# motor.net
KiCad netlist of a schematic drawn in EAGLE
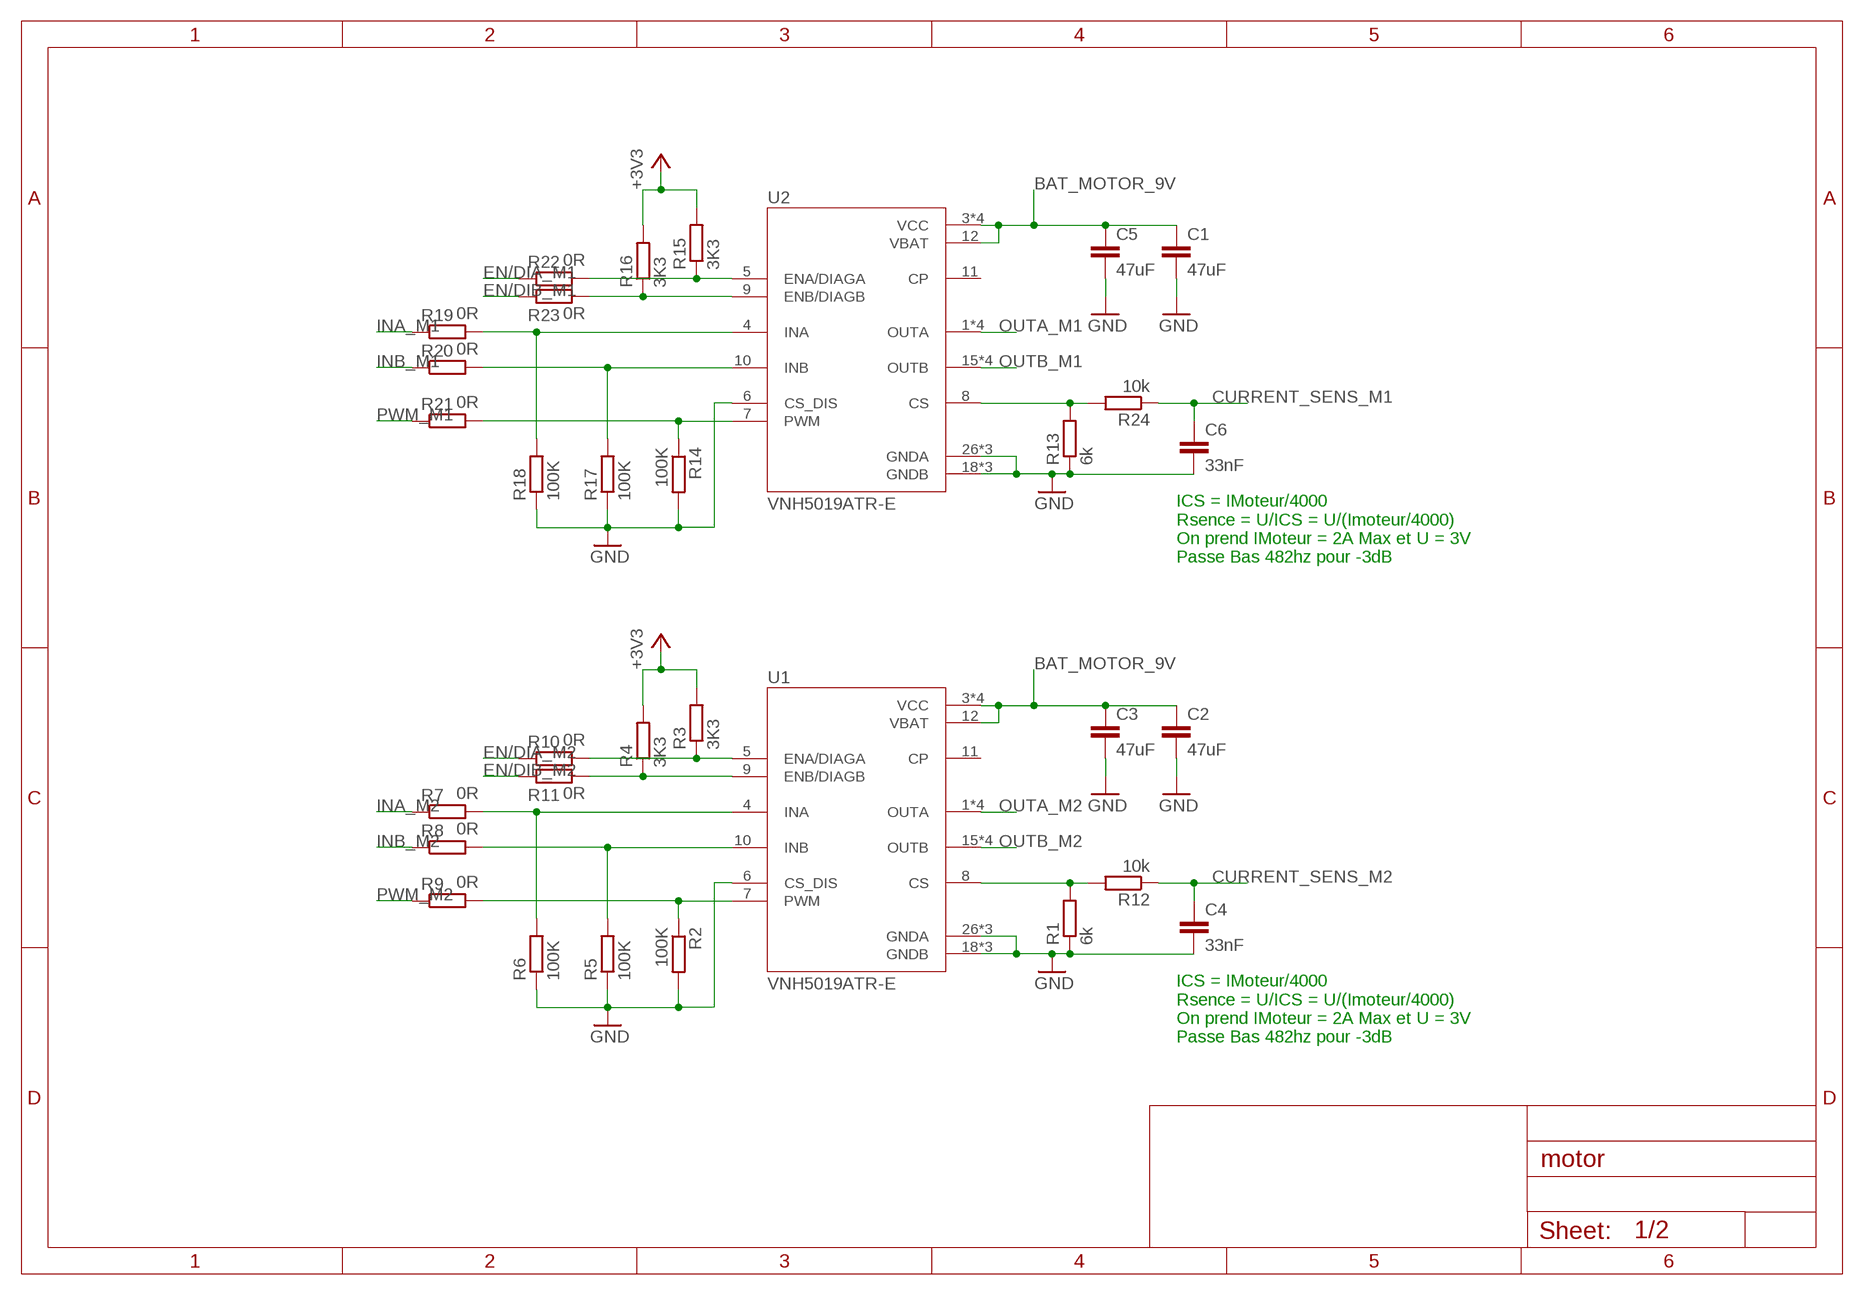
[diagram p0: schematic, sheet 1]
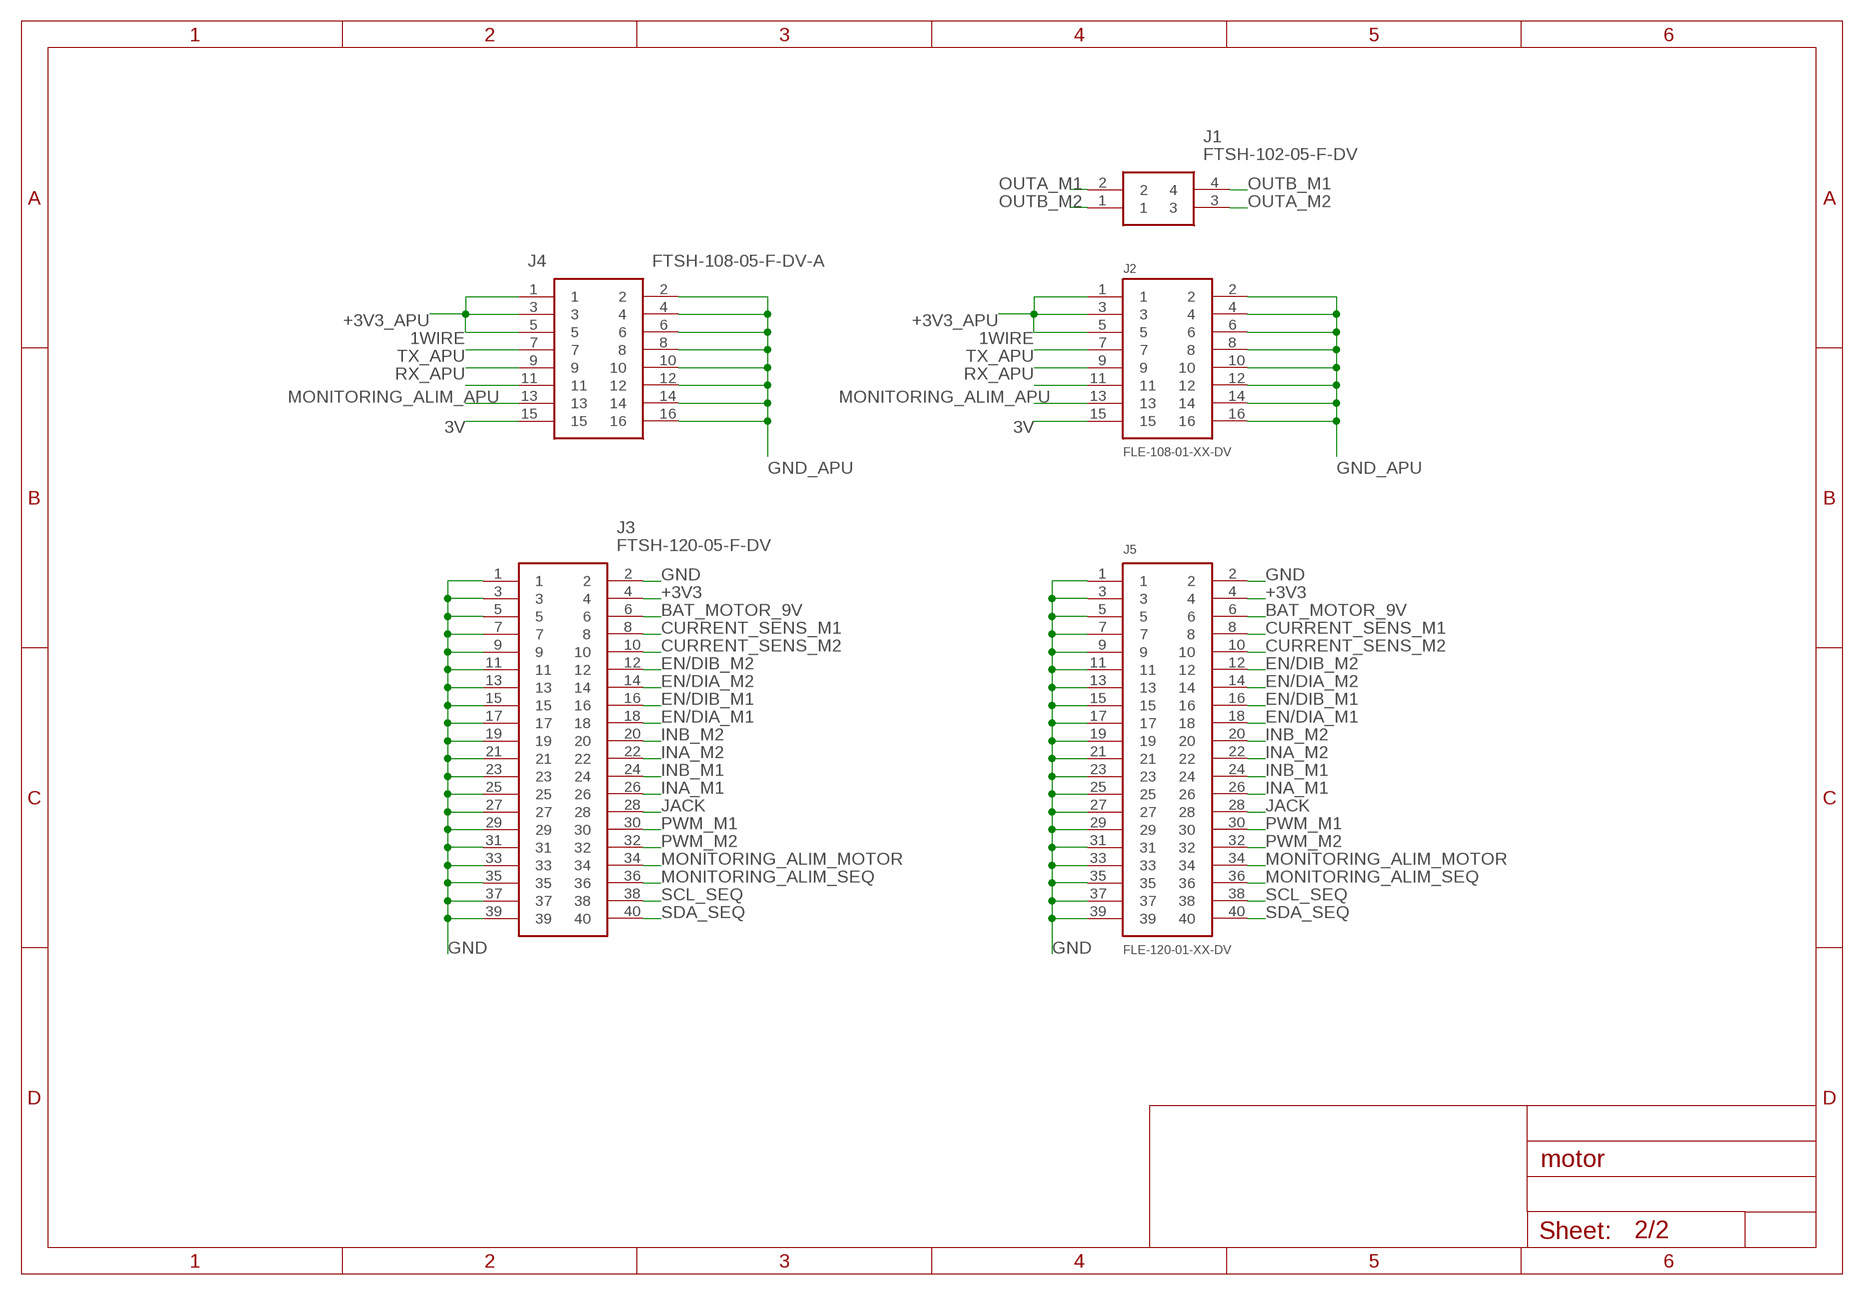
[diagram p1: schematic, sheet 2]

(export (version "E")
  (design (tool "Eeschema 10.0.6"))
  (components
    (comp (ref "J1")
      (value "FTSH-102-05-F-DV")
      (footprint "eagle-import:FTSH-102-XX-YYY-DV")
      (libsource (lib "eagle-import") (part "FTSH-102-05-F-DV"))
    )
    (comp (ref "J2")
      (value "FLE-108-01-XX-DV")
      (footprint "eagle-import:FLE-108-01-XX-DV")
      (fields (field (name "MF") "Samtec") (field (name "MP") "FLE-108-01-G-DV"))
      (libsource (lib "eagle-import") (part "FLE-108-01-XX-DV"))
    )
    (comp (ref "J3")
      (value "FTSH-120-05-F-DV")
      (footprint "eagle-import:FTSH-120-XX-YYY-DV")
      (libsource (lib "eagle-import") (part "FTSH-120-05-F-DV"))
    )
    (comp (ref "J4")
      (value "FTSH-108-05-F-DV-A")
      (footprint "eagle-import:FTSH-108-XX-YYY-DV-A")
      (fields (field (name "MOUSER_PART_NUMBER") "200-FTSH10805FDVA"))
      (libsource (lib "eagle-import") (part "FTSH-108-05-F-DV-A"))
    )
    (comp (ref "J5")
      (value "FLE-120-01-XX-DV")
      (footprint "eagle-import:FLE-120-01-XX-DV")
      (fields (field (name "MF") "Samtec") (field (name "MP") "FLE-120-01-G-DV"))
      (libsource (lib "eagle-import") (part "FLE-120-01-XX-DV"))
    )
    (comp (ref "C1")
      (value "47uF")
      (footprint "eagle-import:C0805")
      (libsource (lib "eagle-import") (part "C-EUC0805"))
    )
    (comp (ref "C2")
      (value "47uF")
      (footprint "eagle-import:C0805")
      (libsource (lib "eagle-import") (part "C-EUC0805"))
    )
    (comp (ref "C3")
      (value "47uF")
      (footprint "eagle-import:C0805")
      (libsource (lib "eagle-import") (part "C-EUC0805"))
    )
    (comp (ref "C4")
      (value "33nF")
      (footprint "eagle-import:C0805")
      (libsource (lib "eagle-import") (part "C-EUC0805"))
    )
    (comp (ref "C5")
      (value "47uF")
      (footprint "eagle-import:C0805")
      (libsource (lib "eagle-import") (part "C-EUC0805"))
    )
    (comp (ref "C6")
      (value "33nF")
      (footprint "eagle-import:C0805")
      (libsource (lib "eagle-import") (part "C-EUC0805"))
    )
    (comp (ref "R1")
      (value "6k")
      (footprint "eagle-import:R0603")
      (libsource (lib "eagle-import") (part "R-EU_R0603"))
    )
    (comp (ref "R2")
      (value "100K")
      (footprint "eagle-import:R0603")
      (libsource (lib "eagle-import") (part "R-EU_R0603"))
    )
    (comp (ref "R3")
      (value "3K3")
      (footprint "eagle-import:R0603")
      (libsource (lib "eagle-import") (part "R-EU_R0603"))
    )
    (comp (ref "R4")
      (value "3K3")
      (footprint "eagle-import:R0603")
      (libsource (lib "eagle-import") (part "R-EU_R0603"))
    )
    (comp (ref "R5")
      (value "100K")
      (footprint "eagle-import:R0603")
      (libsource (lib "eagle-import") (part "R-EU_R0603"))
    )
    (comp (ref "R6")
      (value "100K")
      (footprint "eagle-import:R0603")
      (libsource (lib "eagle-import") (part "R-EU_R0603"))
    )
    (comp (ref "R7")
      (value "0R")
      (footprint "eagle-import:R0603")
      (libsource (lib "eagle-import") (part "R-EU_R0603"))
    )
    (comp (ref "R8")
      (value "0R")
      (footprint "eagle-import:R0603")
      (libsource (lib "eagle-import") (part "R-EU_R0603"))
    )
    (comp (ref "R9")
      (value "0R")
      (footprint "eagle-import:R0603")
      (libsource (lib "eagle-import") (part "R-EU_R0603"))
    )
    (comp (ref "R10")
      (value "0R")
      (footprint "eagle-import:R0603")
      (libsource (lib "eagle-import") (part "R-EU_R0603"))
    )
    (comp (ref "R11")
      (value "0R")
      (footprint "eagle-import:R0603")
      (libsource (lib "eagle-import") (part "R-EU_R0603"))
    )
    (comp (ref "R12")
      (value "10k")
      (footprint "eagle-import:R0603")
      (libsource (lib "eagle-import") (part "R-EU_R0603"))
    )
    (comp (ref "R13")
      (value "6k")
      (footprint "eagle-import:R0603")
      (libsource (lib "eagle-import") (part "R-EU_R0603"))
    )
    (comp (ref "R14")
      (value "100K")
      (footprint "eagle-import:R0603")
      (libsource (lib "eagle-import") (part "R-EU_R0603"))
    )
    (comp (ref "R15")
      (value "3K3")
      (footprint "eagle-import:R0603")
      (libsource (lib "eagle-import") (part "R-EU_R0603"))
    )
    (comp (ref "R16")
      (value "3K3")
      (footprint "eagle-import:R0603")
      (libsource (lib "eagle-import") (part "R-EU_R0603"))
    )
    (comp (ref "R17")
      (value "100K")
      (footprint "eagle-import:R0603")
      (libsource (lib "eagle-import") (part "R-EU_R0603"))
    )
    (comp (ref "R18")
      (value "100K")
      (footprint "eagle-import:R0603")
      (libsource (lib "eagle-import") (part "R-EU_R0603"))
    )
    (comp (ref "R19")
      (value "0R")
      (footprint "eagle-import:R0603")
      (libsource (lib "eagle-import") (part "R-EU_R0603"))
    )
    (comp (ref "R20")
      (value "0R")
      (footprint "eagle-import:R0603")
      (libsource (lib "eagle-import") (part "R-EU_R0603"))
    )
    (comp (ref "R21")
      (value "0R")
      (footprint "eagle-import:R0603")
      (libsource (lib "eagle-import") (part "R-EU_R0603"))
    )
    (comp (ref "R22")
      (value "0R")
      (footprint "eagle-import:R0603")
      (libsource (lib "eagle-import") (part "R-EU_R0603"))
    )
    (comp (ref "R23")
      (value "0R")
      (footprint "eagle-import:R0603")
      (libsource (lib "eagle-import") (part "R-EU_R0603"))
    )
    (comp (ref "R24")
      (value "10k")
      (footprint "eagle-import:R0603")
      (libsource (lib "eagle-import") (part "R-EU_R0603"))
    )
    (comp (ref "U1")
      (value "VNH5019ATR-E")
      (footprint "eagle-import:IC_VNH5019ATR-E")
      (fields (field (name "MF") "STMicroelectronics"))
      (libsource (lib "eagle-import") (part "VNH5019ATR-E"))
    )
    (comp (ref "U2")
      (value "VNH5019ATR-E")
      (footprint "eagle-import:IC_VNH5019ATR-E")
      (fields (field (name "MF") "STMicroelectronics"))
      (libsource (lib "eagle-import") (part "VNH5019ATR-E"))
    )
  )
  (nets
    (net (code "1") (name "+3V3") (class "Default")
      (node (ref "J3") (pin "4") (pinfunction "4_4") (pintype "bidirectional"))
      (node (ref "J5") (pin "4") (pinfunction "4_4") (pintype "bidirectional"))
      (node (ref "R15") (pin "2") (pinfunction "2_2") (pintype "passive"))
      (node (ref "R16") (pin "2") (pinfunction "2_2") (pintype "passive"))
      (node (ref "R3") (pin "2") (pinfunction "2_2") (pintype "passive"))
      (node (ref "R4") (pin "2") (pinfunction "2_2") (pintype "passive"))
    )
    (net (code "2") (name "+3V3_APU") (class "Default")
      (node (ref "J2") (pin "1") (pinfunction "1_1") (pintype "bidirectional"))
      (node (ref "J2") (pin "3") (pinfunction "3_3") (pintype "bidirectional"))
      (node (ref "J2") (pin "5") (pinfunction "5_5") (pintype "bidirectional"))
      (node (ref "J4") (pin "1") (pinfunction "1_1") (pintype "bidirectional"))
      (node (ref "J4") (pin "3") (pinfunction "3_3") (pintype "bidirectional"))
      (node (ref "J4") (pin "5") (pinfunction "5_5") (pintype "bidirectional"))
    )
    (net (code "3") (name "1WIRE") (class "Default")
      (node (ref "J2") (pin "7") (pinfunction "7_7") (pintype "bidirectional"))
      (node (ref "J4") (pin "7") (pinfunction "7_7") (pintype "bidirectional"))
    )
    (net (code "4") (name "3V") (class "Default")
      (node (ref "J2") (pin "15") (pinfunction "15_15") (pintype "bidirectional"))
      (node (ref "J4") (pin "15") (pinfunction "15_15") (pintype "bidirectional"))
    )
    (net (code "5") (name "BAT_MOTOR_9V") (class "Default")
      (node (ref "C1") (pin "1") (pinfunction "1_1") (pintype "passive"))
      (node (ref "C2") (pin "1") (pinfunction "1_1") (pintype "passive"))
      (node (ref "C3") (pin "1") (pinfunction "1_1") (pintype "passive"))
      (node (ref "C5") (pin "1") (pinfunction "1_1") (pintype "passive"))
      (node (ref "J3") (pin "6") (pinfunction "6_6") (pintype "bidirectional"))
      (node (ref "J5") (pin "6") (pinfunction "6_6") (pintype "bidirectional"))
      (node (ref "U1") (pin "12") (pinfunction "VBAT_12") (pintype "power_in"))
      (node (ref "U1") (pin "13") (pinfunction "VCC_13") (pintype "power_in"))
      (node (ref "U1") (pin "23") (pinfunction "VCC_23") (pintype "power_in"))
      (node (ref "U1") (pin "3") (pinfunction "VCC_3") (pintype "power_in"))
      (node (ref "U1") (pin "HS1") (pinfunction "VCC_HS1") (pintype "power_in"))
      (node (ref "U2") (pin "12") (pinfunction "VBAT_12") (pintype "power_in"))
      (node (ref "U2") (pin "13") (pinfunction "VCC_13") (pintype "power_in"))
      (node (ref "U2") (pin "23") (pinfunction "VCC_23") (pintype "power_in"))
      (node (ref "U2") (pin "3") (pinfunction "VCC_3") (pintype "power_in"))
      (node (ref "U2") (pin "HS1") (pinfunction "VCC_HS1") (pintype "power_in"))
    )
    (net (code "6") (name "CURRENT_SENS_M1") (class "Default")
      (node (ref "C6") (pin "1") (pinfunction "1_1") (pintype "passive"))
      (node (ref "J3") (pin "8") (pinfunction "8_8") (pintype "bidirectional"))
      (node (ref "J5") (pin "8") (pinfunction "8_8") (pintype "bidirectional"))
      (node (ref "R24") (pin "1") (pinfunction "1_1") (pintype "passive"))
    )
    (net (code "7") (name "CURRENT_SENS_M2") (class "Default")
      (node (ref "C4") (pin "1") (pinfunction "1_1") (pintype "passive"))
      (node (ref "J3") (pin "10") (pinfunction "10_10") (pintype "bidirectional"))
      (node (ref "J5") (pin "10") (pinfunction "10_10") (pintype "bidirectional"))
      (node (ref "R12") (pin "1") (pinfunction "1_1") (pintype "passive"))
    )
    (net (code "8") (name "EN{slash}DIA_M1") (class "Default")
      (node (ref "J3") (pin "18") (pinfunction "18_18") (pintype "bidirectional"))
      (node (ref "J5") (pin "18") (pinfunction "18_18") (pintype "bidirectional"))
      (node (ref "R22") (pin "1") (pinfunction "1_1") (pintype "passive"))
    )
    (net (code "9") (name "EN{slash}DIA_M2") (class "Default")
      (node (ref "J3") (pin "14") (pinfunction "14_14") (pintype "bidirectional"))
      (node (ref "J5") (pin "14") (pinfunction "14_14") (pintype "bidirectional"))
      (node (ref "R10") (pin "1") (pinfunction "1_1") (pintype "passive"))
    )
    (net (code "10") (name "EN{slash}DIB_M1") (class "Default")
      (node (ref "J3") (pin "16") (pinfunction "16_16") (pintype "bidirectional"))
      (node (ref "J5") (pin "16") (pinfunction "16_16") (pintype "bidirectional"))
      (node (ref "R23") (pin "1") (pinfunction "1_1") (pintype "passive"))
    )
    (net (code "11") (name "EN{slash}DIB_M2") (class "Default")
      (node (ref "J3") (pin "12") (pinfunction "12_12") (pintype "bidirectional"))
      (node (ref "J5") (pin "12") (pinfunction "12_12") (pintype "bidirectional"))
      (node (ref "R11") (pin "1") (pinfunction "1_1") (pintype "passive"))
    )
    (net (code "12") (name "GND") (class "Default")
      (node (ref "C1") (pin "2") (pinfunction "2_2") (pintype "passive"))
      (node (ref "C2") (pin "2") (pinfunction "2_2") (pintype "passive"))
      (node (ref "C3") (pin "2") (pinfunction "2_2") (pintype "passive"))
      (node (ref "C4") (pin "2") (pinfunction "2_2") (pintype "passive"))
      (node (ref "C5") (pin "2") (pinfunction "2_2") (pintype "passive"))
      (node (ref "C6") (pin "2") (pinfunction "2_2") (pintype "passive"))
      (node (ref "J3") (pin "1") (pinfunction "1_1") (pintype "bidirectional"))
      (node (ref "J3") (pin "11") (pinfunction "11_11") (pintype "bidirectional"))
      (node (ref "J3") (pin "13") (pinfunction "13_13") (pintype "bidirectional"))
      (node (ref "J3") (pin "15") (pinfunction "15_15") (pintype "bidirectional"))
      (node (ref "J3") (pin "17") (pinfunction "17_17") (pintype "bidirectional"))
      (node (ref "J3") (pin "19") (pinfunction "19_19") (pintype "bidirectional"))
      (node (ref "J3") (pin "2") (pinfunction "2_2") (pintype "bidirectional"))
      (node (ref "J3") (pin "21") (pinfunction "21_21") (pintype "bidirectional"))
      (node (ref "J3") (pin "23") (pinfunction "23_23") (pintype "bidirectional"))
      (node (ref "J3") (pin "25") (pinfunction "25_25") (pintype "bidirectional"))
      (node (ref "J3") (pin "27") (pinfunction "27_27") (pintype "bidirectional"))
      (node (ref "J3") (pin "29") (pinfunction "29_29") (pintype "bidirectional"))
      (node (ref "J3") (pin "3") (pinfunction "3_3") (pintype "bidirectional"))
      (node (ref "J3") (pin "31") (pinfunction "31_31") (pintype "bidirectional"))
      (node (ref "J3") (pin "33") (pinfunction "33_33") (pintype "bidirectional"))
      (node (ref "J3") (pin "35") (pinfunction "35_35") (pintype "bidirectional"))
      (node (ref "J3") (pin "37") (pinfunction "37_37") (pintype "bidirectional"))
      (node (ref "J3") (pin "39") (pinfunction "39_39") (pintype "bidirectional"))
      (node (ref "J3") (pin "5") (pinfunction "5_5") (pintype "bidirectional"))
      (node (ref "J3") (pin "7") (pinfunction "7_7") (pintype "bidirectional"))
      (node (ref "J3") (pin "9") (pinfunction "9_9") (pintype "bidirectional"))
      (node (ref "J5") (pin "1") (pinfunction "1_1") (pintype "bidirectional"))
      (node (ref "J5") (pin "11") (pinfunction "11_11") (pintype "bidirectional"))
      (node (ref "J5") (pin "13") (pinfunction "13_13") (pintype "bidirectional"))
      (node (ref "J5") (pin "15") (pinfunction "15_15") (pintype "bidirectional"))
      (node (ref "J5") (pin "17") (pinfunction "17_17") (pintype "bidirectional"))
      (node (ref "J5") (pin "19") (pinfunction "19_19") (pintype "bidirectional"))
      (node (ref "J5") (pin "2") (pinfunction "2_2") (pintype "bidirectional"))
      (node (ref "J5") (pin "21") (pinfunction "21_21") (pintype "bidirectional"))
      (node (ref "J5") (pin "23") (pinfunction "23_23") (pintype "bidirectional"))
      (node (ref "J5") (pin "25") (pinfunction "25_25") (pintype "bidirectional"))
      (node (ref "J5") (pin "27") (pinfunction "27_27") (pintype "bidirectional"))
      (node (ref "J5") (pin "29") (pinfunction "29_29") (pintype "bidirectional"))
      (node (ref "J5") (pin "3") (pinfunction "3_3") (pintype "bidirectional"))
      (node (ref "J5") (pin "31") (pinfunction "31_31") (pintype "bidirectional"))
      (node (ref "J5") (pin "33") (pinfunction "33_33") (pintype "bidirectional"))
      (node (ref "J5") (pin "35") (pinfunction "35_35") (pintype "bidirectional"))
      (node (ref "J5") (pin "37") (pinfunction "37_37") (pintype "bidirectional"))
      (node (ref "J5") (pin "39") (pinfunction "39_39") (pintype "bidirectional"))
      (node (ref "J5") (pin "5") (pinfunction "5_5") (pintype "bidirectional"))
      (node (ref "J5") (pin "7") (pinfunction "7_7") (pintype "bidirectional"))
      (node (ref "J5") (pin "9") (pinfunction "9_9") (pintype "bidirectional"))
      (node (ref "R1") (pin "1") (pinfunction "1_1") (pintype "passive"))
      (node (ref "R13") (pin "1") (pinfunction "1_1") (pintype "passive"))
      (node (ref "R14") (pin "2") (pinfunction "2_2") (pintype "passive"))
      (node (ref "R17") (pin "1") (pinfunction "1_1") (pintype "passive"))
      (node (ref "R18") (pin "1") (pinfunction "1_1") (pintype "passive"))
      (node (ref "R2") (pin "2") (pinfunction "2_2") (pintype "passive"))
      (node (ref "R5") (pin "1") (pinfunction "1_1") (pintype "passive"))
      (node (ref "R6") (pin "1") (pinfunction "1_1") (pintype "passive"))
      (node (ref "U1") (pin "18") (pinfunction "GNDB_18") (pintype "power_in"))
      (node (ref "U1") (pin "19") (pinfunction "GNDB_19") (pintype "power_in"))
      (node (ref "U1") (pin "20") (pinfunction "GNDB_20") (pintype "power_in"))
      (node (ref "U1") (pin "26") (pinfunction "GNDA_26") (pintype "power_in"))
      (node (ref "U1") (pin "27") (pinfunction "GNDA_27") (pintype "power_in"))
      (node (ref "U1") (pin "28") (pinfunction "GNDA_28") (pintype "power_in"))
      (node (ref "U1") (pin "6") (pinfunction "CS_DIS_6") (pintype "input"))
      (node (ref "U2") (pin "18") (pinfunction "GNDB_18") (pintype "power_in"))
      (node (ref "U2") (pin "19") (pinfunction "GNDB_19") (pintype "power_in"))
      (node (ref "U2") (pin "20") (pinfunction "GNDB_20") (pintype "power_in"))
      (node (ref "U2") (pin "26") (pinfunction "GNDA_26") (pintype "power_in"))
      (node (ref "U2") (pin "27") (pinfunction "GNDA_27") (pintype "power_in"))
      (node (ref "U2") (pin "28") (pinfunction "GNDA_28") (pintype "power_in"))
      (node (ref "U2") (pin "6") (pinfunction "CS_DIS_6") (pintype "input"))
    )
    (net (code "13") (name "GND_APU") (class "Default")
      (node (ref "J2") (pin "10") (pinfunction "10_10") (pintype "bidirectional"))
      (node (ref "J2") (pin "12") (pinfunction "12_12") (pintype "bidirectional"))
      (node (ref "J2") (pin "14") (pinfunction "14_14") (pintype "bidirectional"))
      (node (ref "J2") (pin "16") (pinfunction "16_16") (pintype "bidirectional"))
      (node (ref "J2") (pin "2") (pinfunction "2_2") (pintype "bidirectional"))
      (node (ref "J2") (pin "4") (pinfunction "4_4") (pintype "bidirectional"))
      (node (ref "J2") (pin "6") (pinfunction "6_6") (pintype "bidirectional"))
      (node (ref "J2") (pin "8") (pinfunction "8_8") (pintype "bidirectional"))
      (node (ref "J4") (pin "10") (pinfunction "10_10") (pintype "bidirectional"))
      (node (ref "J4") (pin "12") (pinfunction "12_12") (pintype "bidirectional"))
      (node (ref "J4") (pin "14") (pinfunction "14_14") (pintype "bidirectional"))
      (node (ref "J4") (pin "16") (pinfunction "16_16") (pintype "bidirectional"))
      (node (ref "J4") (pin "2") (pinfunction "2_2") (pintype "bidirectional"))
      (node (ref "J4") (pin "4") (pinfunction "4_4") (pintype "bidirectional"))
      (node (ref "J4") (pin "6") (pinfunction "6_6") (pintype "bidirectional"))
      (node (ref "J4") (pin "8") (pinfunction "8_8") (pintype "bidirectional"))
    )
    (net (code "14") (name "INA_M1") (class "Default")
      (node (ref "J3") (pin "26") (pinfunction "26_26") (pintype "bidirectional"))
      (node (ref "J5") (pin "26") (pinfunction "26_26") (pintype "bidirectional"))
      (node (ref "R19") (pin "1") (pinfunction "1_1") (pintype "passive"))
    )
    (net (code "15") (name "INA_M2") (class "Default")
      (node (ref "J3") (pin "22") (pinfunction "22_22") (pintype "bidirectional"))
      (node (ref "J5") (pin "22") (pinfunction "22_22") (pintype "bidirectional"))
      (node (ref "R7") (pin "1") (pinfunction "1_1") (pintype "passive"))
    )
    (net (code "16") (name "INB_M1") (class "Default")
      (node (ref "J3") (pin "24") (pinfunction "24_24") (pintype "bidirectional"))
      (node (ref "J5") (pin "24") (pinfunction "24_24") (pintype "bidirectional"))
      (node (ref "R20") (pin "1") (pinfunction "1_1") (pintype "passive"))
    )
    (net (code "17") (name "INB_M2") (class "Default")
      (node (ref "J3") (pin "20") (pinfunction "20_20") (pintype "bidirectional"))
      (node (ref "J5") (pin "20") (pinfunction "20_20") (pintype "bidirectional"))
      (node (ref "R8") (pin "1") (pinfunction "1_1") (pintype "passive"))
    )
    (net (code "18") (name "JACK") (class "Default")
      (node (ref "J3") (pin "28") (pinfunction "28_28") (pintype "bidirectional"))
      (node (ref "J5") (pin "28") (pinfunction "28_28") (pintype "bidirectional"))
    )
    (net (code "19") (name "MONITORING_ALIM_APU") (class "Default")
      (node (ref "J2") (pin "13") (pinfunction "13_13") (pintype "bidirectional"))
      (node (ref "J4") (pin "13") (pinfunction "13_13") (pintype "bidirectional"))
    )
    (net (code "20") (name "MONITORING_ALIM_MOTOR") (class "Default")
      (node (ref "J3") (pin "34") (pinfunction "34_34") (pintype "bidirectional"))
      (node (ref "J5") (pin "34") (pinfunction "34_34") (pintype "bidirectional"))
    )
    (net (code "21") (name "MONITORING_ALIM_SEQ") (class "Default")
      (node (ref "J3") (pin "36") (pinfunction "36_36") (pintype "bidirectional"))
      (node (ref "J5") (pin "36") (pinfunction "36_36") (pintype "bidirectional"))
    )
    (net (code "22") (name "Net-(U1-CS)") (class "Default")
      (node (ref "R1") (pin "2") (pinfunction "2_2") (pintype "passive"))
      (node (ref "R12") (pin "2") (pinfunction "2_2") (pintype "passive"))
      (node (ref "U1") (pin "8") (pinfunction "CS_8") (pintype "output"))
    )
    (net (code "23") (name "Net-(U1-ENA{slash}DIAGA)") (class "Default")
      (node (ref "R10") (pin "2") (pinfunction "2_2") (pintype "passive"))
      (node (ref "R3") (pin "1") (pinfunction "1_1") (pintype "passive"))
      (node (ref "U1") (pin "5") (pinfunction "ENA/DIAGA_5") (pintype "input"))
    )
    (net (code "24") (name "Net-(U1-ENB{slash}DIAGB)") (class "Default")
      (node (ref "R11") (pin "2") (pinfunction "2_2") (pintype "passive"))
      (node (ref "R4") (pin "1") (pinfunction "1_1") (pintype "passive"))
      (node (ref "U1") (pin "9") (pinfunction "ENB/DIAGB_9") (pintype "input"))
    )
    (net (code "25") (name "Net-(U1-INA)") (class "Default")
      (node (ref "R6") (pin "2") (pinfunction "2_2") (pintype "passive"))
      (node (ref "R7") (pin "2") (pinfunction "2_2") (pintype "passive"))
      (node (ref "U1") (pin "4") (pinfunction "INA_4") (pintype "input"))
    )
    (net (code "26") (name "Net-(U1-INB)") (class "Default")
      (node (ref "R5") (pin "2") (pinfunction "2_2") (pintype "passive"))
      (node (ref "R8") (pin "2") (pinfunction "2_2") (pintype "passive"))
      (node (ref "U1") (pin "10") (pinfunction "INB_10") (pintype "input"))
    )
    (net (code "27") (name "Net-(U1-PWM)") (class "Default")
      (node (ref "R2") (pin "1") (pinfunction "1_1") (pintype "passive"))
      (node (ref "R9") (pin "2") (pinfunction "2_2") (pintype "passive"))
      (node (ref "U1") (pin "7") (pinfunction "PWM_7") (pintype "input"))
    )
    (net (code "28") (name "Net-(U2-CS)") (class "Default")
      (node (ref "R13") (pin "2") (pinfunction "2_2") (pintype "passive"))
      (node (ref "R24") (pin "2") (pinfunction "2_2") (pintype "passive"))
      (node (ref "U2") (pin "8") (pinfunction "CS_8") (pintype "output"))
    )
    (net (code "29") (name "Net-(U2-ENA{slash}DIAGA)") (class "Default")
      (node (ref "R15") (pin "1") (pinfunction "1_1") (pintype "passive"))
      (node (ref "R22") (pin "2") (pinfunction "2_2") (pintype "passive"))
      (node (ref "U2") (pin "5") (pinfunction "ENA/DIAGA_5") (pintype "input"))
    )
    (net (code "30") (name "Net-(U2-ENB{slash}DIAGB)") (class "Default")
      (node (ref "R16") (pin "1") (pinfunction "1_1") (pintype "passive"))
      (node (ref "R23") (pin "2") (pinfunction "2_2") (pintype "passive"))
      (node (ref "U2") (pin "9") (pinfunction "ENB/DIAGB_9") (pintype "input"))
    )
    (net (code "31") (name "Net-(U2-INA)") (class "Default")
      (node (ref "R18") (pin "2") (pinfunction "2_2") (pintype "passive"))
      (node (ref "R19") (pin "2") (pinfunction "2_2") (pintype "passive"))
      (node (ref "U2") (pin "4") (pinfunction "INA_4") (pintype "input"))
    )
    (net (code "32") (name "Net-(U2-INB)") (class "Default")
      (node (ref "R17") (pin "2") (pinfunction "2_2") (pintype "passive"))
      (node (ref "R20") (pin "2") (pinfunction "2_2") (pintype "passive"))
      (node (ref "U2") (pin "10") (pinfunction "INB_10") (pintype "input"))
    )
    (net (code "33") (name "Net-(U2-PWM)") (class "Default")
      (node (ref "R14") (pin "1") (pinfunction "1_1") (pintype "passive"))
      (node (ref "R21") (pin "2") (pinfunction "2_2") (pintype "passive"))
      (node (ref "U2") (pin "7") (pinfunction "PWM_7") (pintype "input"))
    )
    (net (code "34") (name "OUTA_M1") (class "Default")
      (node (ref "J1") (pin "2") (pinfunction "2_2") (pintype "bidirectional"))
      (node (ref "U2") (pin "1") (pinfunction "OUTA_1") (pintype "output"))
      (node (ref "U2") (pin "25") (pinfunction "OUTA_25") (pintype "output"))
      (node (ref "U2") (pin "30") (pinfunction "OUTA_30") (pintype "output"))
      (node (ref "U2") (pin "HS2") (pinfunction "OUTA_HS2") (pintype "output"))
    )
    (net (code "35") (name "OUTA_M2") (class "Default")
      (node (ref "J1") (pin "3") (pinfunction "3_3") (pintype "bidirectional"))
      (node (ref "U1") (pin "1") (pinfunction "OUTA_1") (pintype "output"))
      (node (ref "U1") (pin "25") (pinfunction "OUTA_25") (pintype "output"))
      (node (ref "U1") (pin "30") (pinfunction "OUTA_30") (pintype "output"))
      (node (ref "U1") (pin "HS2") (pinfunction "OUTA_HS2") (pintype "output"))
    )
    (net (code "36") (name "OUTB_M1") (class "Default")
      (node (ref "J1") (pin "4") (pinfunction "4_4") (pintype "bidirectional"))
      (node (ref "U2") (pin "15") (pinfunction "OUTB_15") (pintype "output"))
      (node (ref "U2") (pin "16") (pinfunction "OUTB_16") (pintype "output"))
      (node (ref "U2") (pin "21") (pinfunction "OUTB_21") (pintype "output"))
      (node (ref "U2") (pin "HS3") (pinfunction "OUTB_HS3") (pintype "output"))
    )
    (net (code "37") (name "OUTB_M2") (class "Default")
      (node (ref "J1") (pin "1") (pinfunction "1_1") (pintype "bidirectional"))
      (node (ref "U1") (pin "15") (pinfunction "OUTB_15") (pintype "output"))
      (node (ref "U1") (pin "16") (pinfunction "OUTB_16") (pintype "output"))
      (node (ref "U1") (pin "21") (pinfunction "OUTB_21") (pintype "output"))
      (node (ref "U1") (pin "HS3") (pinfunction "OUTB_HS3") (pintype "output"))
    )
    (net (code "38") (name "PWM_M1") (class "Default")
      (node (ref "J3") (pin "30") (pinfunction "30_30") (pintype "bidirectional"))
      (node (ref "J5") (pin "30") (pinfunction "30_30") (pintype "bidirectional"))
      (node (ref "R21") (pin "1") (pinfunction "1_1") (pintype "passive"))
    )
    (net (code "39") (name "PWM_M2") (class "Default")
      (node (ref "J3") (pin "32") (pinfunction "32_32") (pintype "bidirectional"))
      (node (ref "J5") (pin "32") (pinfunction "32_32") (pintype "bidirectional"))
      (node (ref "R9") (pin "1") (pinfunction "1_1") (pintype "passive"))
    )
    (net (code "40") (name "RX_APU") (class "Default")
      (node (ref "J2") (pin "11") (pinfunction "11_11") (pintype "bidirectional"))
      (node (ref "J4") (pin "11") (pinfunction "11_11") (pintype "bidirectional"))
    )
    (net (code "41") (name "SCL_SEQ") (class "Default")
      (node (ref "J3") (pin "38") (pinfunction "38_38") (pintype "bidirectional"))
      (node (ref "J5") (pin "38") (pinfunction "38_38") (pintype "bidirectional"))
    )
    (net (code "42") (name "SDA_SEQ") (class "Default")
      (node (ref "J3") (pin "40") (pinfunction "40_40") (pintype "bidirectional"))
      (node (ref "J5") (pin "40") (pinfunction "40_40") (pintype "bidirectional"))
    )
    (net (code "43") (name "TX_APU") (class "Default")
      (node (ref "J2") (pin "9") (pinfunction "9_9") (pintype "bidirectional"))
      (node (ref "J4") (pin "9") (pinfunction "9_9") (pintype "bidirectional"))
    )
    (net (code "44") (name "unconnected-(U1-CP-Pad11)") (class "Default")
      (node (ref "U1") (pin "11") (pinfunction "CP_11") (pintype "output"))
    )
    (net (code "45") (name "unconnected-(U2-CP-Pad11)") (class "Default")
      (node (ref "U2") (pin "11") (pinfunction "CP_11") (pintype "output"))
    )
  )
)
